# Kello_uC.net
KiCad netlist of a schematic drawn in Altium Designer
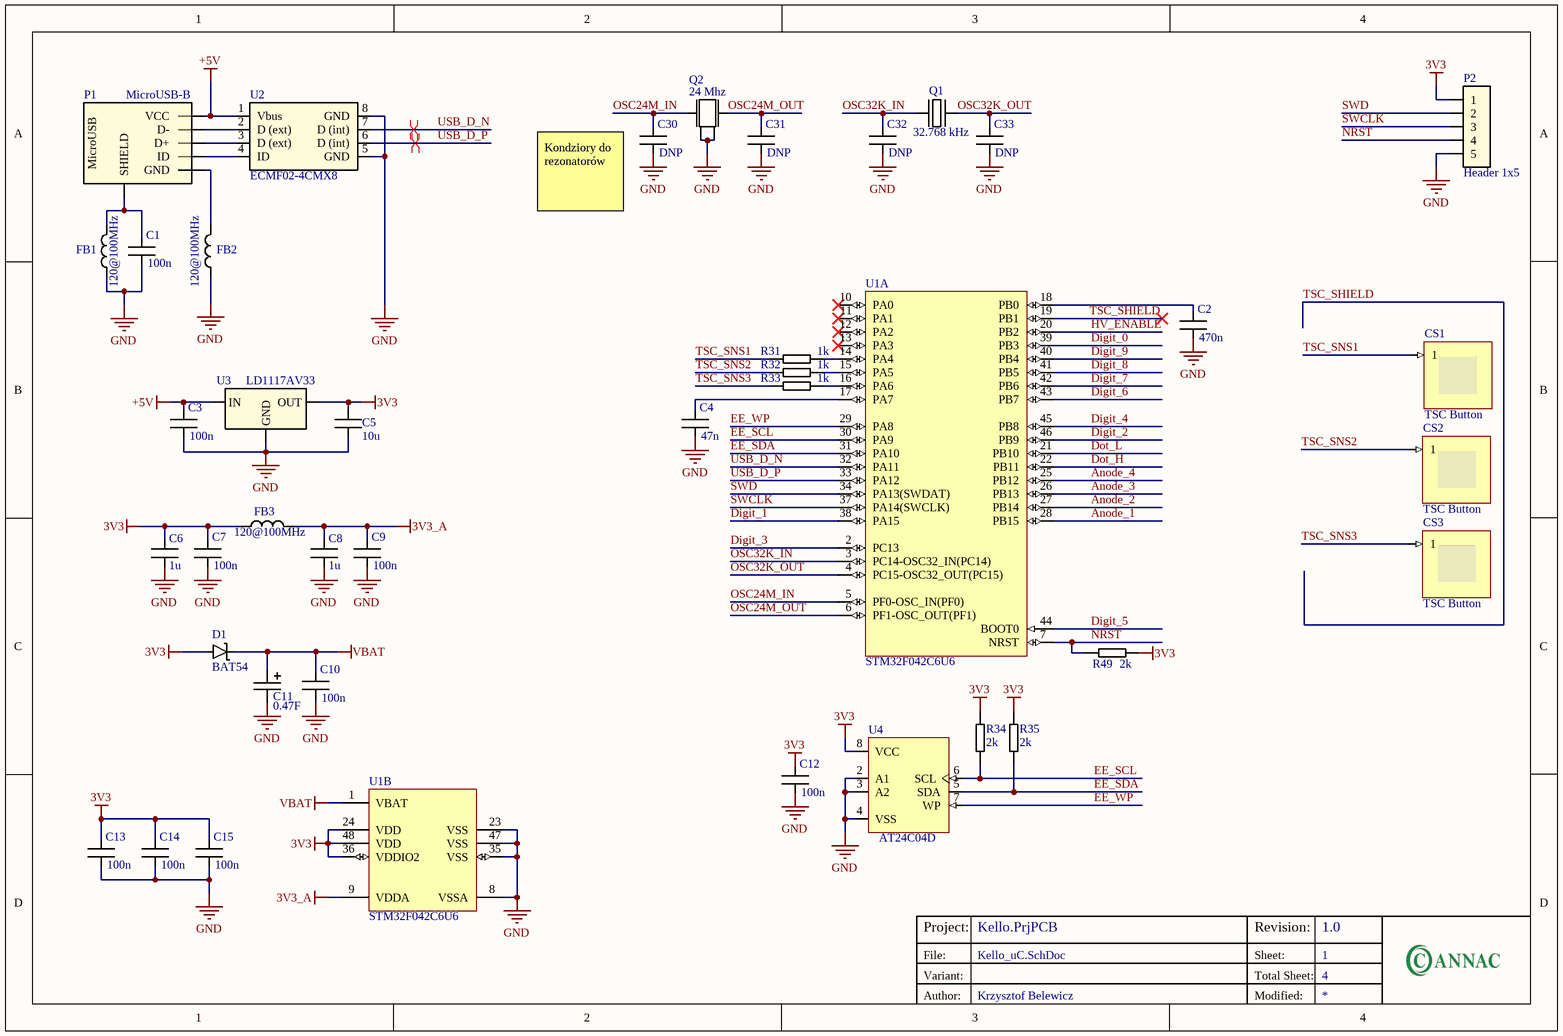
[diagram p0: Kello_uC.SchDoc]

(export (version "E")
  (design (tool "Eeschema 10.0.6"))
  (components
    (comp (ref "C1")
      (value "100n")
      (footprint "CAPC1608N")
      (description "Capacitor")
      (fields (field (name "TOLERANCE") "-20/+80%"))
      (libsource (lib "RLC") (part "Capacitor"))
    )
    (comp (ref "C2")
      (value "470n")
      (footprint "CAPC1608N")
      (description "Capacitor")
      (fields (field (name "TOLERANCE") "10%"))
      (libsource (lib "RLC") (part "Capacitor"))
    )
    (comp (ref "C3")
      (value "100n")
      (footprint "CAPC1608N")
      (description "Capacitor")
      (fields (field (name "TOLERANCE") "-20/+80%"))
      (libsource (lib "RLC") (part "Capacitor"))
    )
    (comp (ref "C4")
      (value "47n")
      (footprint "CAPC1608N")
      (description "Capacitor")
      (fields (field (name "TOLERANCE") "10%"))
      (libsource (lib "RLC") (part "Capacitor"))
    )
    (comp (ref "C5")
      (value "10u")
      (footprint "CAPC1608N")
      (description "Capacitor")
      (fields (field (name "TOLERANCE") "20%"))
      (libsource (lib "RLC") (part "Capacitor"))
    )
    (comp (ref "C6")
      (value "1u")
      (footprint "CAPC1608N")
      (description "Capacitor")
      (fields (field (name "TOLERANCE") "10%"))
      (libsource (lib "RLC") (part "Capacitor"))
    )
    (comp (ref "C7")
      (value "100n")
      (footprint "CAPC1608N")
      (description "Capacitor")
      (fields (field (name "TOLERANCE") "-20/+80%"))
      (libsource (lib "RLC") (part "Capacitor"))
    )
    (comp (ref "C8")
      (value "1u")
      (footprint "CAPC1608N")
      (description "Capacitor")
      (fields (field (name "TOLERANCE") "10%"))
      (libsource (lib "RLC") (part "Capacitor"))
    )
    (comp (ref "C9")
      (value "100n")
      (footprint "CAPC1608N")
      (description "Capacitor")
      (fields (field (name "TOLERANCE") "-20/+80%"))
      (libsource (lib "RLC") (part "Capacitor"))
    )
    (comp (ref "C10")
      (value "100n")
      (footprint "CAPC1608N")
      (description "Capacitor")
      (fields (field (name "TOLERANCE") "-20/+80%"))
      (libsource (lib "RLC") (part "Capacitor"))
    )
    (comp (ref "C11")
      (value "0.47F")
      (footprint "FGH0V474ZF")
      (description "Kondensator: elektrolityczny; 0.47F; 3,5VDC; ESR:25Ω; SMD; -20÷+80%")
      (libsource (lib "KEMET") (part "FGH0V474ZF"))
    )
    (comp (ref "C12")
      (value "100n")
      (footprint "CAPC1608N")
      (description "Capacitor")
      (fields (field (name "TOLERANCE") "-20/+80%"))
      (libsource (lib "RLC") (part "Capacitor"))
    )
    (comp (ref "C13")
      (value "100n")
      (footprint "CAPC1608N")
      (description "Capacitor")
      (fields (field (name "TOLERANCE") "-20/+80%"))
      (libsource (lib "RLC") (part "Capacitor"))
    )
    (comp (ref "C14")
      (value "100n")
      (footprint "CAPC1608N")
      (description "Capacitor")
      (fields (field (name "TOLERANCE") "-20/+80%"))
      (libsource (lib "RLC") (part "Capacitor"))
    )
    (comp (ref "C15")
      (value "100n")
      (footprint "CAPC1608N")
      (description "Capacitor")
      (fields (field (name "TOLERANCE") "-20/+80%"))
      (libsource (lib "RLC") (part "Capacitor"))
    )
    (comp (ref "C30")
      (value "DNP")
      (footprint "CAPC1608N")
      (description "Capacitor")
      (libsource (lib "RLC") (part "Capacitor"))
    )
    (comp (ref "C31")
      (value "DNP")
      (footprint "CAPC1608N")
      (description "Capacitor")
      (libsource (lib "RLC") (part "Capacitor"))
    )
    (comp (ref "C32")
      (value "DNP")
      (footprint "CAPC1608N")
      (description "Capacitor")
      (libsource (lib "RLC") (part "Capacitor"))
    )
    (comp (ref "C33")
      (value "DNP")
      (footprint "CAPC1608N")
      (description "Capacitor")
      (libsource (lib "RLC") (part "Capacitor"))
    )
    (comp (ref "CS1")
      (value "TSC Button")
      (description "QTouch Button")
      (libsource (lib "Atmel QTouch") (part "QTouchButton"))
    )
    (comp (ref "CS2")
      (value "TSC Button")
      (description "QTouch Button")
      (libsource (lib "Atmel QTouch") (part "QTouchButton"))
    )
    (comp (ref "CS3")
      (value "TSC Button")
      (description "QTouch Button")
      (libsource (lib "Atmel QTouch") (part "QTouchButton"))
    )
    (comp (ref "D1")
      (value "BAT54")
      (footprint "SOD-523F")
      (description "Fairchild BAT54XV2, Schottky, 200mA, 30V")
      (fields (field (name "MANUFACTURER") "Fairchild") (field (name "MANUFACTURER PART NUMBER") "BAT54XV2"))
      (libsource (lib "Diodes") (part "BAT54XV2"))
    )
    (comp (ref "FB1")
      (value "120@100MHz")
      (footprint "INDC1608N")
      (description "Ferrite Bead")
      (libsource (lib "") (part "Inductor_1"))
    )
    (comp (ref "FB2")
      (value "120@100MHz")
      (footprint "INDC1608N")
      (description "Ferrite Bead")
      (libsource (lib "") (part "Inductor_1"))
    )
    (comp (ref "FB3")
      (value "120@100MHz")
      (footprint "INDC1608N")
      (description "Ferrite Bead")
      (libsource (lib "RLC") (part "Inductor"))
    )
    (comp (ref "P1")
      (value "MicroUSB-B")
      (footprint "MicroUSB-B (47346-0001)")
      (description "Molex MicroUSB-B, SMD (P/N 47346-0001)")
      (libsource (lib "Molex_HighSpeed") (part "47346-0001"))
    )
    (comp (ref "P2")
      (value "Header 1x5")
      (footprint "Header 1x5, Male, 2.54mm, Straight, THT")
      (description "Pin header, 1x5, 2.54mm")
      (libsource (lib "Header") (part "Header 1x5"))
    )
    (comp (ref "Q1")
      (value "32.768 kHz")
      (footprint "IL3X2")
      (fields (field (name "Comment") "Crystal 2 pin"))
      (libsource (lib "Crystal") (part "Crystal 2 pin"))
    )
    (comp (ref "Q2")
      (value "24 Mhz")
      (footprint "CFPX-5")
      (fields (field (name "Comment") "24Mhz"))
      (libsource (lib "Crystals") (part "Crystal 4 pin"))
    )
    (comp (ref "R31")
      (value "1k")
      (footprint "RESC1608N")
      (description "Resistor")
      (fields (field (name "TOLERANCE") "1%") (field (name "POWER") "0.1W"))
      (libsource (lib "RLC") (part "Resistor"))
    )
    (comp (ref "R32")
      (value "1k")
      (footprint "RESC1608N")
      (description "Resistor")
      (fields (field (name "TOLERANCE") "1%") (field (name "POWER") "0.1W"))
      (libsource (lib "RLC") (part "Resistor"))
    )
    (comp (ref "R33")
      (value "1k")
      (footprint "RESC1608N")
      (description "Resistor")
      (fields (field (name "TOLERANCE") "1%") (field (name "POWER") "0.1W"))
      (libsource (lib "RLC") (part "Resistor"))
    )
    (comp (ref "R34")
      (value "2k")
      (footprint "RESC1608N")
      (description "Resistor")
      (fields (field (name "TOLERANCE") "1%") (field (name "POWER") "0.1W"))
      (libsource (lib "RLC") (part "Resistor"))
    )
    (comp (ref "R35")
      (value "2k")
      (footprint "RESC1608N")
      (description "Resistor")
      (fields (field (name "TOLERANCE") "1%") (field (name "POWER") "0.1W"))
      (libsource (lib "RLC") (part "Resistor"))
    )
    (comp (ref "R49")
      (value "2k")
      (footprint "RESC1608N")
      (description "Resistor")
      (fields (field (name "TOLERANCE") "1%") (field (name "POWER") "0.1W"))
      (libsource (lib "RLC") (part "Resistor"))
    )
    (comp (ref "U1")
      (value "STM32F042C6U6")
      (footprint "STMicroelectronics STM32 F0:STM-UFQFPN48_N")
      (description "ARM Cortex-M0 32-bit MCU, 32 KB Flash, 6 KB Internal RAM, 38 I/Os, 48-pin UFQFPN, -40 to 85 degC")
      (libsource (lib "STMicroelectronics STM32 F0") (part "STM32F042C6U6"))
    )
    (comp (ref "U2")
      (value "ECMF02-4CMX8")
      (footprint "uQFN-8")
      (description "STMicroelectronics Common Mode Filter with ESD protection, USB compatible")
      (fields (field (name "MANUFACTURER") "STMicroelectronics"))
      (libsource (lib "STMicroelectronics_Protective") (part "ECMF02-4CMX8"))
    )
    (comp (ref "U3")
      (value "LD1117AV33")
      (footprint "SOT223_N")
      (description "Stabilizator napięcia; LDO, liniowy, nieregulowany; 3,3V; 1A; SMD")
      (libsource (lib "STMicroelectronics_Power") (part "LD1117AS33TR"))
    )
    (comp (ref "U4")
      (value "AT24C04D")
      (footprint "DFN-MC8")
      (description "4Kbit, 1MHz, 1.7V-3.6V, I2C Serial EEPROM, 8-Pin DFN, Industrial Temperature, Tape and Reel")
      (libsource (lib "Microchip Memory I2C Serial EEPROM") (part "AT24C04D-MAHM-T"))
    )
  )
  (nets
    (net (code "1") (name "+5V") (class "Default")
      (node (ref "C3") (pin "2") (pinfunction "2_2") (pintype "passive"))
      (node (ref "P1") (pin "1") (pinfunction "VCC_1") (pintype "passive"))
      (node (ref "U2") (pin "1") (pinfunction "Vbus_1") (pintype "passive"))
      (node (ref "U3") (pin "3") (pinfunction "IN_3") (pintype "passive"))
    )
    (net (code "2") (name "/Anode_1") (class "Default")
      (node (ref "U1") (pin "28") (pinfunction "PB15_28") (pintype "bidirectional"))
    )
    (net (code "3") (name "/Anode_2") (class "Default")
      (node (ref "U1") (pin "27") (pinfunction "PB14_27") (pintype "bidirectional"))
    )
    (net (code "4") (name "/Anode_3") (class "Default")
      (node (ref "U1") (pin "26") (pinfunction "PB13_26") (pintype "bidirectional"))
    )
    (net (code "5") (name "/Anode_4") (class "Default")
      (node (ref "U1") (pin "25") (pinfunction "PB12_25") (pintype "bidirectional"))
    )
    (net (code "6") (name "/Digit_0") (class "Default")
      (node (ref "U1") (pin "39") (pinfunction "PB3_39") (pintype "bidirectional"))
    )
    (net (code "7") (name "/Digit_1") (class "Default")
      (node (ref "U1") (pin "38") (pinfunction "PA15_38") (pintype "bidirectional"))
    )
    (net (code "8") (name "/Digit_2") (class "Default")
      (node (ref "U1") (pin "46") (pinfunction "PB9_46") (pintype "bidirectional"))
    )
    (net (code "9") (name "/Digit_3") (class "Default")
      (node (ref "U1") (pin "2") (pinfunction "PC13_2") (pintype "bidirectional"))
    )
    (net (code "10") (name "/Digit_4") (class "Default")
      (node (ref "U1") (pin "45") (pinfunction "PB8_45") (pintype "bidirectional"))
    )
    (net (code "11") (name "/Digit_5") (class "Default")
      (node (ref "U1") (pin "44") (pinfunction "BOOT0_44") (pintype "input"))
    )
    (net (code "12") (name "/Digit_6") (class "Default")
      (node (ref "U1") (pin "43") (pinfunction "PB7_43") (pintype "bidirectional"))
    )
    (net (code "13") (name "/Digit_7") (class "Default")
      (node (ref "U1") (pin "42") (pinfunction "PB6_42") (pintype "bidirectional"))
    )
    (net (code "14") (name "/Digit_8") (class "Default")
      (node (ref "U1") (pin "41") (pinfunction "PB5_41") (pintype "bidirectional"))
    )
    (net (code "15") (name "/Digit_9") (class "Default")
      (node (ref "U1") (pin "40") (pinfunction "PB4_40") (pintype "bidirectional"))
    )
    (net (code "16") (name "/Dot_H") (class "Default")
      (node (ref "U1") (pin "22") (pinfunction "PB11_22") (pintype "bidirectional"))
    )
    (net (code "17") (name "/Dot_L") (class "Default")
      (node (ref "U1") (pin "21") (pinfunction "PB10_21") (pintype "bidirectional"))
    )
    (net (code "18") (name "/EE_SCL") (class "Default")
      (node (ref "R34") (pin "2") (pinfunction "2_2") (pintype "passive"))
      (node (ref "U1") (pin "30") (pinfunction "PA9_30") (pintype "bidirectional"))
      (node (ref "U4") (pin "6") (pinfunction "SCL_6") (pintype "input"))
    )
    (net (code "19") (name "/EE_SDA") (class "Default")
      (node (ref "R35") (pin "2") (pinfunction "2_2") (pintype "passive"))
      (node (ref "U1") (pin "31") (pinfunction "PA10_31") (pintype "bidirectional"))
      (node (ref "U4") (pin "5") (pinfunction "SDA_5") (pintype "bidirectional"))
    )
    (net (code "20") (name "/EE_WP") (class "Default")
      (node (ref "U1") (pin "29") (pinfunction "PA8_29") (pintype "bidirectional"))
      (node (ref "U4") (pin "7") (pinfunction "WP_7") (pintype "input"))
    )
    (net (code "21") (name "/HV_ENABLE") (class "Default")
      (node (ref "U1") (pin "20") (pinfunction "PB2_20") (pintype "bidirectional"))
    )
    (net (code "22") (name "/NRST") (class "Default")
      (node (ref "P2") (pin "4") (pinfunction "4_4") (pintype "passive"))
      (node (ref "R49") (pin "1") (pinfunction "1_1") (pintype "passive"))
      (node (ref "U1") (pin "7") (pinfunction "NRST_7") (pintype "bidirectional"))
    )
    (net (code "23") (name "/OSC24M_IN") (class "Default")
      (node (ref "C30") (pin "2") (pinfunction "2_2") (pintype "passive"))
      (node (ref "Q2") (pin "1") (pinfunction "1_1") (pintype "passive"))
      (node (ref "U1") (pin "5") (pinfunction "PF0-OSC_IN(PF0)_5") (pintype "bidirectional"))
    )
    (net (code "24") (name "/OSC24M_OUT") (class "Default")
      (node (ref "C31") (pin "2") (pinfunction "2_2") (pintype "passive"))
      (node (ref "Q2") (pin "3") (pinfunction "3_3") (pintype "passive"))
      (node (ref "U1") (pin "6") (pinfunction "PF1-OSC_OUT(PF1)_6") (pintype "bidirectional"))
    )
    (net (code "25") (name "/OSC32K_IN") (class "Default")
      (node (ref "C32") (pin "2") (pinfunction "2_2") (pintype "passive"))
      (node (ref "Q1") (pin "1") (pinfunction "1_1") (pintype "passive"))
      (node (ref "U1") (pin "3") (pinfunction "PC14-OSC32_IN(PC14)_3") (pintype "bidirectional"))
    )
    (net (code "26") (name "/OSC32K_OUT") (class "Default")
      (node (ref "C33") (pin "2") (pinfunction "2_2") (pintype "passive"))
      (node (ref "Q1") (pin "2") (pinfunction "2_2") (pintype "passive"))
      (node (ref "U1") (pin "4") (pinfunction "PC15-OSC32_OUT(PC15)_4") (pintype "bidirectional"))
    )
    (net (code "27") (name "/SWCLK") (class "Default")
      (node (ref "P2") (pin "3") (pinfunction "3_3") (pintype "passive"))
      (node (ref "U1") (pin "37") (pinfunction "PA14(SWCLK)_37") (pintype "bidirectional"))
    )
    (net (code "28") (name "/SWD") (class "Default")
      (node (ref "P2") (pin "2") (pinfunction "2_2") (pintype "passive"))
      (node (ref "U1") (pin "34") (pinfunction "PA13(SWDAT)_34") (pintype "bidirectional"))
    )
    (net (code "29") (name "/TSC_SHIELD") (class "Default")
      (node (ref "U1") (pin "19") (pinfunction "PB1_19") (pintype "bidirectional+no_connect"))
    )
    (net (code "30") (name "/TSC_SNS1") (class "Default")
      (node (ref "CS1") (pin "1") (pinfunction "1_1") (pintype "input"))
      (node (ref "R31") (pin "1") (pinfunction "1_1") (pintype "passive"))
    )
    (net (code "31") (name "/TSC_SNS2") (class "Default")
      (node (ref "CS2") (pin "1") (pinfunction "1_1") (pintype "input"))
      (node (ref "R32") (pin "1") (pinfunction "1_1") (pintype "passive"))
    )
    (net (code "32") (name "/TSC_SNS3") (class "Default")
      (node (ref "CS3") (pin "1") (pinfunction "1_1") (pintype "input"))
      (node (ref "R33") (pin "1") (pinfunction "1_1") (pintype "passive"))
    )
    (net (code "33") (name "/USB_D_N") (class "Default")
      (node (ref "U1") (pin "32") (pinfunction "PA11_32") (pintype "bidirectional"))
      (node (ref "U2") (pin "7") (pinfunction "D_(int)_7") (pintype "passive"))
    )
    (net (code "34") (name "/USB_D_P") (class "Default")
      (node (ref "U1") (pin "33") (pinfunction "PA12_33") (pintype "bidirectional"))
      (node (ref "U2") (pin "6") (pinfunction "D_(int)_6") (pintype "passive"))
    )
    (net (code "35") (name "3V3") (class "Default")
      (node (ref "C12") (pin "2") (pinfunction "2_2") (pintype "passive"))
      (node (ref "C13") (pin "2") (pinfunction "2_2") (pintype "passive"))
      (node (ref "C14") (pin "2") (pinfunction "2_2") (pintype "passive"))
      (node (ref "C15") (pin "2") (pinfunction "2_2") (pintype "passive"))
      (node (ref "C5") (pin "2") (pinfunction "2_2") (pintype "passive"))
      (node (ref "C6") (pin "2") (pinfunction "2_2") (pintype "passive"))
      (node (ref "C7") (pin "2") (pinfunction "2_2") (pintype "passive"))
      (node (ref "D1") (pin "A") (pinfunction "A_A") (pintype "passive"))
      (node (ref "FB3") (pin "1") (pinfunction "1_1") (pintype "passive"))
      (node (ref "P2") (pin "1") (pinfunction "1_1") (pintype "passive"))
      (node (ref "R34") (pin "1") (pinfunction "1_1") (pintype "passive"))
      (node (ref "R35") (pin "1") (pinfunction "1_1") (pintype "passive"))
      (node (ref "R49") (pin "2") (pinfunction "2_2") (pintype "passive"))
      (node (ref "U1") (pin "24") (pinfunction "VDD_24") (pintype "power_in"))
      (node (ref "U1") (pin "36") (pinfunction "VDDIO2_36") (pintype "bidirectional"))
      (node (ref "U1") (pin "48") (pinfunction "VDD_48") (pintype "power_in"))
      (node (ref "U3") (pin "2") (pinfunction "OUT_2") (pintype "passive"))
      (node (ref "U4") (pin "8") (pinfunction "VCC_8") (pintype "power_in"))
    )
    (net (code "36") (name "3V3_A") (class "Default")
      (node (ref "C8") (pin "2") (pinfunction "2_2") (pintype "passive"))
      (node (ref "C9") (pin "2") (pinfunction "2_2") (pintype "passive"))
      (node (ref "FB3") (pin "2") (pinfunction "2_2") (pintype "passive"))
      (node (ref "U1") (pin "9") (pinfunction "VDDA_9") (pintype "power_in"))
    )
    (net (code "37") (name "GND") (class "Default")
      (node (ref "C1") (pin "1") (pinfunction "1_1") (pintype "passive"))
      (node (ref "C10") (pin "1") (pinfunction "1_1") (pintype "passive"))
      (node (ref "C11") (pin "2") (pinfunction "2_2") (pintype "passive"))
      (node (ref "C12") (pin "1") (pinfunction "1_1") (pintype "passive"))
      (node (ref "C13") (pin "1") (pinfunction "1_1") (pintype "passive"))
      (node (ref "C14") (pin "1") (pinfunction "1_1") (pintype "passive"))
      (node (ref "C15") (pin "1") (pinfunction "1_1") (pintype "passive"))
      (node (ref "C2") (pin "1") (pinfunction "1_1") (pintype "passive"))
      (node (ref "C3") (pin "1") (pinfunction "1_1") (pintype "passive"))
      (node (ref "C30") (pin "1") (pinfunction "1_1") (pintype "passive"))
      (node (ref "C31") (pin "1") (pinfunction "1_1") (pintype "passive"))
      (node (ref "C32") (pin "1") (pinfunction "1_1") (pintype "passive"))
      (node (ref "C33") (pin "1") (pinfunction "1_1") (pintype "passive"))
      (node (ref "C4") (pin "1") (pinfunction "1_1") (pintype "passive"))
      (node (ref "C5") (pin "1") (pinfunction "1_1") (pintype "passive"))
      (node (ref "C6") (pin "1") (pinfunction "1_1") (pintype "passive"))
      (node (ref "C7") (pin "1") (pinfunction "1_1") (pintype "passive"))
      (node (ref "C8") (pin "1") (pinfunction "1_1") (pintype "passive"))
      (node (ref "C9") (pin "1") (pinfunction "1_1") (pintype "passive"))
      (node (ref "FB1") (pin "2") (pinfunction "2_2") (pintype "passive"))
      (node (ref "FB2") (pin "2") (pinfunction "2_2") (pintype "passive"))
      (node (ref "P2") (pin "5") (pinfunction "5_5") (pintype "passive"))
      (node (ref "Q2") (pin "2") (pinfunction "2_2") (pintype "passive"))
      (node (ref "Q2") (pin "4") (pinfunction "4_4") (pintype "passive"))
      (node (ref "U1") (pin "23") (pinfunction "VSS_23") (pintype "power_in"))
      (node (ref "U1") (pin "35") (pinfunction "VSS_35") (pintype "bidirectional"))
      (node (ref "U1") (pin "47") (pinfunction "VSS_47") (pintype "power_in"))
      (node (ref "U1") (pin "8") (pinfunction "VSSA_8") (pintype "power_in"))
      (node (ref "U2") (pin "5") (pinfunction "GND_5") (pintype "passive"))
      (node (ref "U2") (pin "8") (pinfunction "GND_8") (pintype "passive"))
      (node (ref "U3") (pin "1") (pinfunction "GND_1") (pintype "passive"))
      (node (ref "U4") (pin "2") (pinfunction "A1_2") (pintype "passive"))
      (node (ref "U4") (pin "3") (pinfunction "A2_3") (pintype "passive"))
      (node (ref "U4") (pin "4") (pinfunction "VSS_4") (pintype "power_in"))
    )
    (net (code "38") (name "Net-(P1-D+)") (class "Default")
      (node (ref "P1") (pin "3") (pinfunction "D+_3") (pintype "passive"))
      (node (ref "U2") (pin "3") (pinfunction "D_(ext)_3") (pintype "passive"))
    )
    (net (code "39") (name "Net-(P1-D-)") (class "Default")
      (node (ref "P1") (pin "2") (pinfunction "D-_2") (pintype "passive"))
      (node (ref "U2") (pin "2") (pinfunction "D_(ext)_2") (pintype "passive"))
    )
    (net (code "40") (name "Net-(P1-GND)") (class "Default")
      (node (ref "FB2") (pin "1") (pinfunction "1_1") (pintype "passive"))
      (node (ref "P1") (pin "5") (pinfunction "GND_5") (pintype "passive"))
    )
    (net (code "41") (name "Net-(P1-ID)") (class "Default")
      (node (ref "P1") (pin "4") (pinfunction "ID_4") (pintype "passive"))
      (node (ref "U2") (pin "4") (pinfunction "ID_4") (pintype "passive"))
    )
    (net (code "42") (name "Net-(P1-SHIELD)") (class "Default")
      (node (ref "C1") (pin "2") (pinfunction "2_2") (pintype "passive"))
      (node (ref "FB1") (pin "1") (pinfunction "1_1") (pintype "passive"))
      (node (ref "P1") (pin "6") (pinfunction "SHIELD_6") (pintype "passive"))
    )
    (net (code "43") (name "Net-(U1A-PA4)") (class "Default")
      (node (ref "R31") (pin "2") (pinfunction "2_2") (pintype "passive"))
      (node (ref "U1") (pin "14") (pinfunction "PA4_14") (pintype "bidirectional"))
    )
    (net (code "44") (name "Net-(U1A-PA5)") (class "Default")
      (node (ref "R32") (pin "2") (pinfunction "2_2") (pintype "passive"))
      (node (ref "U1") (pin "15") (pinfunction "PA5_15") (pintype "bidirectional"))
    )
    (net (code "45") (name "Net-(U1A-PA6)") (class "Default")
      (node (ref "R33") (pin "2") (pinfunction "2_2") (pintype "passive"))
      (node (ref "U1") (pin "16") (pinfunction "PA6_16") (pintype "bidirectional"))
    )
    (net (code "46") (name "Net-(U1A-PA7)") (class "Default")
      (node (ref "C4") (pin "2") (pinfunction "2_2") (pintype "passive"))
      (node (ref "U1") (pin "17") (pinfunction "PA7_17") (pintype "bidirectional"))
    )
    (net (code "47") (name "Net-(U1A-PB0)") (class "Default")
      (node (ref "C2") (pin "2") (pinfunction "2_2") (pintype "passive"))
      (node (ref "U1") (pin "18") (pinfunction "PB0_18") (pintype "bidirectional"))
    )
    (net (code "48") (name "VBAT") (class "Default")
      (node (ref "C10") (pin "2") (pinfunction "2_2") (pintype "passive"))
      (node (ref "C11") (pin "1") (pinfunction "1_1") (pintype "passive"))
      (node (ref "D1") (pin "K") (pinfunction "K_K") (pintype "passive"))
      (node (ref "U1") (pin "1") (pinfunction "VBAT_1") (pintype "power_in"))
    )
    (net (code "49") (name "unconnected-(U1A-PA0-Pad10)") (class "Default")
      (node (ref "U1") (pin "10") (pinfunction "PA0_10") (pintype "bidirectional+no_connect"))
    )
    (net (code "50") (name "unconnected-(U1A-PA1-Pad11)") (class "Default")
      (node (ref "U1") (pin "11") (pinfunction "PA1_11") (pintype "bidirectional+no_connect"))
    )
    (net (code "51") (name "unconnected-(U1A-PA2-Pad12)") (class "Default")
      (node (ref "U1") (pin "12") (pinfunction "PA2_12") (pintype "bidirectional+no_connect"))
    )
    (net (code "52") (name "unconnected-(U1A-PA3-Pad13)") (class "Default")
      (node (ref "U1") (pin "13") (pinfunction "PA3_13") (pintype "bidirectional+no_connect"))
    )
  )
)
